# low_level_contoller_board.net
KiCad netlist of a schematic drawn in EAGLE
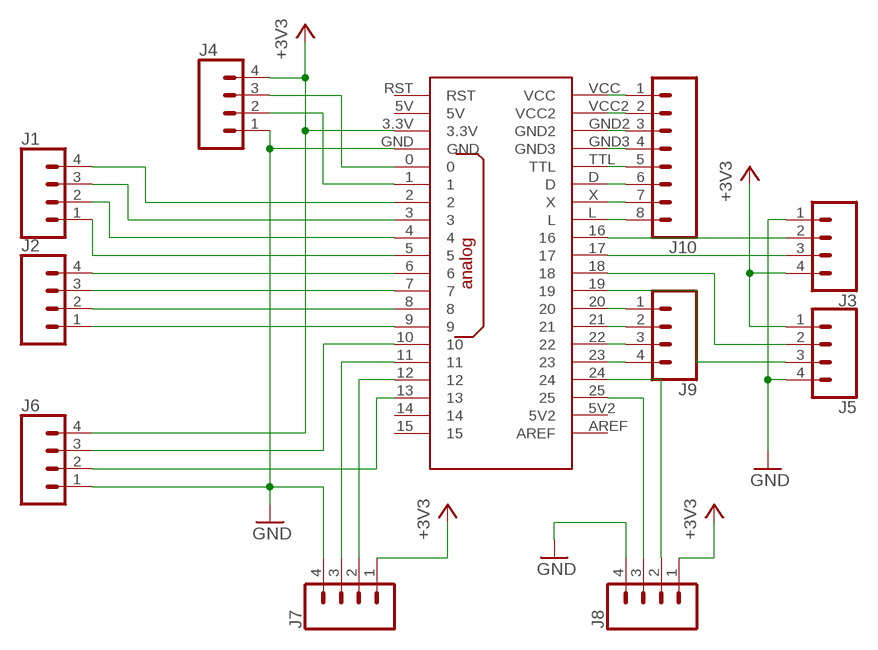
[diagram p0: schematic, sheet 1]

(export (version "E")
  (design (tool "Eeschema 10.0.6"))
  (components
    (comp (ref "J1")
      (value "CONN_04POLAR")
      (footprint "eagle-import:MOLEX-1X4")
      (libsource (lib "eagle-import") (part "CONN_04POLAR"))
    )
    (comp (ref "J2")
      (value "CONN_04POLAR")
      (footprint "eagle-import:MOLEX-1X4")
      (libsource (lib "eagle-import") (part "CONN_04POLAR"))
    )
    (comp (ref "J3")
      (value "CONN_04")
      (footprint "eagle-import:1X04")
      (libsource (lib "eagle-import") (part "CONN_04"))
    )
    (comp (ref "J4")
      (value "CONN_04")
      (footprint "eagle-import:1X04")
      (libsource (lib "eagle-import") (part "CONN_04"))
    )
    (comp (ref "J5")
      (value "CONN_04")
      (footprint "eagle-import:1X04")
      (libsource (lib "eagle-import") (part "CONN_04"))
    )
    (comp (ref "J6")
      (value "CONN_04")
      (footprint "eagle-import:1X04")
      (libsource (lib "eagle-import") (part "CONN_04"))
    )
    (comp (ref "J7")
      (value "CONN_04")
      (footprint "eagle-import:1X04")
      (libsource (lib "eagle-import") (part "CONN_04"))
    )
    (comp (ref "J8")
      (value "CONN_04")
      (footprint "eagle-import:1X04")
      (libsource (lib "eagle-import") (part "CONN_04"))
    )
    (comp (ref "J9")
      (value "CONN_04")
      (footprint "eagle-import:1X04")
      (libsource (lib "eagle-import") (part "CONN_04"))
    )
    (comp (ref "J10")
      (value "CONN_08\"")
      (footprint "eagle-import:1X08")
      (libsource (lib "eagle-import") (part "CONN_08{dblquote}"))
    )
    (comp (ref "U$1")
      (value "OPENCM9.04")
      (footprint "eagle-import:OPENCM9.04")
      (libsource (lib "eagle-import") (part "OPENCM9.04"))
    )
  )
  (nets
    (net (code "1") (name "+3V3") (class "Default")
      (node (ref "J3") (pin "4") (pinfunction "4_4") (pintype "passive"))
      (node (ref "J4") (pin "4") (pinfunction "4_4") (pintype "passive"))
      (node (ref "J5") (pin "1") (pinfunction "1_1") (pintype "passive"))
      (node (ref "J6") (pin "4") (pinfunction "4_4") (pintype "passive"))
      (node (ref "J7") (pin "1") (pinfunction "1_1") (pintype "passive"))
      (node (ref "J8") (pin "1") (pinfunction "1_1") (pintype "passive"))
      (node (ref "U$1") (pin "3.3V") (pinfunction "3.3V_3.3V") (pintype "bidirectional"))
    )
    (net (code "2") (name "GND") (class "Default")
      (node (ref "J3") (pin "1") (pinfunction "1_1") (pintype "passive"))
      (node (ref "J4") (pin "1") (pinfunction "1_1") (pintype "passive"))
      (node (ref "J5") (pin "4") (pinfunction "4_4") (pintype "passive"))
      (node (ref "J6") (pin "1") (pinfunction "1_1") (pintype "passive"))
      (node (ref "J7") (pin "4") (pinfunction "4_4") (pintype "passive"))
      (node (ref "J8") (pin "4") (pinfunction "4_4") (pintype "passive"))
      (node (ref "U$1") (pin "GND") (pinfunction "GND_GND") (pintype "bidirectional"))
    )
    (net (code "3") (name "Net-(J1-Pad1)") (class "Default")
      (node (ref "J1") (pin "1") (pinfunction "1_1") (pintype "passive"))
      (node (ref "U$1") (pin "5") (pinfunction "5_5") (pintype "bidirectional"))
    )
    (net (code "4") (name "Net-(J1-Pad2)") (class "Default")
      (node (ref "J1") (pin "2") (pinfunction "2_2") (pintype "passive"))
      (node (ref "U$1") (pin "4") (pinfunction "4_4") (pintype "bidirectional"))
    )
    (net (code "5") (name "Net-(J1-Pad3)") (class "Default")
      (node (ref "J1") (pin "3") (pinfunction "3_3") (pintype "passive"))
      (node (ref "U$1") (pin "3") (pinfunction "3_3") (pintype "bidirectional"))
    )
    (net (code "6") (name "Net-(J1-Pad4)") (class "Default")
      (node (ref "J1") (pin "4") (pinfunction "4_4") (pintype "passive"))
      (node (ref "U$1") (pin "2") (pinfunction "2_2") (pintype "bidirectional"))
    )
    (net (code "7") (name "Net-(J2-Pad1)") (class "Default")
      (node (ref "J2") (pin "1") (pinfunction "1_1") (pintype "passive"))
      (node (ref "U$1") (pin "9") (pinfunction "9_9") (pintype "bidirectional"))
    )
    (net (code "8") (name "Net-(J2-Pad2)") (class "Default")
      (node (ref "J2") (pin "2") (pinfunction "2_2") (pintype "passive"))
      (node (ref "U$1") (pin "8") (pinfunction "8_8") (pintype "bidirectional"))
    )
    (net (code "9") (name "Net-(J2-Pad3)") (class "Default")
      (node (ref "J2") (pin "3") (pinfunction "3_3") (pintype "passive"))
      (node (ref "U$1") (pin "7") (pinfunction "7_7") (pintype "bidirectional"))
    )
    (net (code "10") (name "Net-(J2-Pad4)") (class "Default")
      (node (ref "J2") (pin "4") (pinfunction "4_4") (pintype "passive"))
      (node (ref "U$1") (pin "6") (pinfunction "6_6") (pintype "bidirectional"))
    )
    (net (code "11") (name "Net-(J3-Pad2)") (class "Default")
      (node (ref "J3") (pin "2") (pinfunction "2_2") (pintype "passive"))
      (node (ref "U$1") (pin "16") (pinfunction "16_16") (pintype "bidirectional"))
    )
    (net (code "12") (name "Net-(J3-Pad3)") (class "Default")
      (node (ref "J3") (pin "3") (pinfunction "3_3") (pintype "passive"))
      (node (ref "U$1") (pin "17") (pinfunction "17_17") (pintype "bidirectional"))
    )
    (net (code "13") (name "Net-(J4-Pad2)") (class "Default")
      (node (ref "J4") (pin "2") (pinfunction "2_2") (pintype "passive"))
      (node (ref "U$1") (pin "1") (pinfunction "1_1") (pintype "bidirectional"))
    )
    (net (code "14") (name "Net-(J4-Pad3)") (class "Default")
      (node (ref "J4") (pin "3") (pinfunction "3_3") (pintype "passive"))
      (node (ref "U$1") (pin "0") (pinfunction "0_0") (pintype "bidirectional"))
    )
    (net (code "15") (name "Net-(J5-Pad2)") (class "Default")
      (node (ref "J5") (pin "2") (pinfunction "2_2") (pintype "passive"))
      (node (ref "U$1") (pin "18") (pinfunction "18_18") (pintype "bidirectional"))
    )
    (net (code "16") (name "Net-(J5-Pad3)") (class "Default")
      (node (ref "J5") (pin "3") (pinfunction "3_3") (pintype "passive"))
      (node (ref "U$1") (pin "19") (pinfunction "19_19") (pintype "bidirectional"))
    )
    (net (code "17") (name "Net-(J6-Pad2)") (class "Default")
      (node (ref "J6") (pin "2") (pinfunction "2_2") (pintype "passive"))
      (node (ref "U$1") (pin "13") (pinfunction "13_13") (pintype "bidirectional"))
    )
    (net (code "18") (name "Net-(J6-Pad3)") (class "Default")
      (node (ref "J6") (pin "3") (pinfunction "3_3") (pintype "passive"))
      (node (ref "U$1") (pin "10") (pinfunction "10_10") (pintype "bidirectional"))
    )
    (net (code "19") (name "Net-(J7-Pad2)") (class "Default")
      (node (ref "J7") (pin "2") (pinfunction "2_2") (pintype "passive"))
      (node (ref "U$1") (pin "12") (pinfunction "12_12") (pintype "bidirectional"))
    )
    (net (code "20") (name "Net-(J7-Pad3)") (class "Default")
      (node (ref "J7") (pin "3") (pinfunction "3_3") (pintype "passive"))
      (node (ref "U$1") (pin "11") (pinfunction "11_11") (pintype "bidirectional"))
    )
    (net (code "21") (name "Net-(J8-Pad2)") (class "Default")
      (node (ref "J8") (pin "2") (pinfunction "2_2") (pintype "passive"))
      (node (ref "U$1") (pin "24") (pinfunction "24_24") (pintype "bidirectional"))
    )
    (net (code "22") (name "Net-(J8-Pad3)") (class "Default")
      (node (ref "J8") (pin "3") (pinfunction "3_3") (pintype "passive"))
      (node (ref "U$1") (pin "25") (pinfunction "25_25") (pintype "bidirectional"))
    )
    (net (code "23") (name "Net-(J9-Pad1)") (class "Default")
      (node (ref "J9") (pin "1") (pinfunction "1_1") (pintype "passive"))
      (node (ref "U$1") (pin "20") (pinfunction "20_20") (pintype "bidirectional"))
    )
    (net (code "24") (name "Net-(J9-Pad2)") (class "Default")
      (node (ref "J9") (pin "2") (pinfunction "2_2") (pintype "passive"))
      (node (ref "U$1") (pin "21") (pinfunction "21_21") (pintype "bidirectional"))
    )
    (net (code "25") (name "Net-(J9-Pad3)") (class "Default")
      (node (ref "J9") (pin "3") (pinfunction "3_3") (pintype "passive"))
      (node (ref "U$1") (pin "22") (pinfunction "22_22") (pintype "bidirectional"))
    )
    (net (code "26") (name "Net-(J9-Pad4)") (class "Default")
      (node (ref "J9") (pin "4") (pinfunction "4_4") (pintype "passive"))
      (node (ref "U$1") (pin "23") (pinfunction "23_23") (pintype "bidirectional"))
    )
    (net (code "27") (name "Net-(J10-Pad1)") (class "Default")
      (node (ref "J10") (pin "1") (pinfunction "1_1") (pintype "passive"))
      (node (ref "U$1") (pin "VCC") (pinfunction "VCC_VCC") (pintype "bidirectional"))
    )
    (net (code "28") (name "Net-(J10-Pad2)") (class "Default")
      (node (ref "J10") (pin "2") (pinfunction "2_2") (pintype "passive"))
      (node (ref "U$1") (pin "VCC2") (pinfunction "VCC2_VCC2") (pintype "bidirectional"))
    )
    (net (code "29") (name "Net-(J10-Pad3)") (class "Default")
      (node (ref "J10") (pin "3") (pinfunction "3_3") (pintype "passive"))
      (node (ref "U$1") (pin "GND2") (pinfunction "GND2_GND2") (pintype "bidirectional"))
    )
    (net (code "30") (name "Net-(J10-Pad4)") (class "Default")
      (node (ref "J10") (pin "4") (pinfunction "4_4") (pintype "passive"))
      (node (ref "U$1") (pin "GND3") (pinfunction "GND3_GND3") (pintype "bidirectional"))
    )
    (net (code "31") (name "Net-(J10-Pad5)") (class "Default")
      (node (ref "J10") (pin "5") (pinfunction "5_5") (pintype "passive"))
      (node (ref "U$1") (pin "TTL") (pinfunction "TTL_TTL") (pintype "bidirectional"))
    )
    (net (code "32") (name "Net-(J10-Pad6)") (class "Default")
      (node (ref "J10") (pin "6") (pinfunction "6_6") (pintype "passive"))
      (node (ref "U$1") (pin "D") (pinfunction "D_D") (pintype "bidirectional"))
    )
    (net (code "33") (name "Net-(J10-Pad7)") (class "Default")
      (node (ref "J10") (pin "7") (pinfunction "7_7") (pintype "passive"))
      (node (ref "U$1") (pin "X") (pinfunction "X_X") (pintype "bidirectional"))
    )
    (net (code "34") (name "Net-(J10-Pad8)") (class "Default")
      (node (ref "J10") (pin "8") (pinfunction "8_8") (pintype "passive"))
      (node (ref "U$1") (pin "L") (pinfunction "L_L") (pintype "bidirectional"))
    )
    (net (code "35") (name "unconnected-(U$1-Pad5V)") (class "Default")
      (node (ref "U$1") (pin "5V") (pinfunction "5V_5V") (pintype "bidirectional"))
    )
    (net (code "36") (name "unconnected-(U$1-Pad5V2)") (class "Default")
      (node (ref "U$1") (pin "5V2") (pinfunction "5V2_5V2") (pintype "bidirectional"))
    )
    (net (code "37") (name "unconnected-(U$1-Pad14)") (class "Default")
      (node (ref "U$1") (pin "14") (pinfunction "14_14") (pintype "bidirectional"))
    )
    (net (code "38") (name "unconnected-(U$1-Pad15)") (class "Default")
      (node (ref "U$1") (pin "15") (pinfunction "15_15") (pintype "bidirectional"))
    )
    (net (code "39") (name "unconnected-(U$1-PadAREF)") (class "Default")
      (node (ref "U$1") (pin "AREF") (pinfunction "AREF_AREF") (pintype "bidirectional"))
    )
    (net (code "40") (name "unconnected-(U$1-PadRST)") (class "Default")
      (node (ref "U$1") (pin "RST") (pinfunction "RST_RST") (pintype "bidirectional"))
    )
  )
)
